# hld.net
KiCad netlist of a schematic drawn in EAGLE
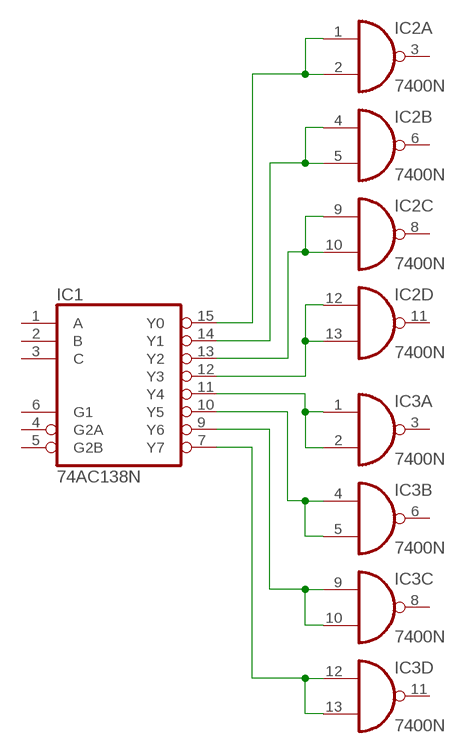
[diagram p0: schematic, sheet 1]

(export (version "E")
  (design (tool "Eeschema 10.0.6"))
  (components
    (comp (ref "IC1")
      (value "74AC138N")
      (footprint "eagle-import:DIL16")
      (libsource (lib "eagle-import") (part "74138NAC"))
    )
    (comp (ref "IC2")
      (value "7400N")
      (footprint "eagle-import:DIL14")
      (libsource (lib "eagle-import") (part "7400N"))
    )
    (comp (ref "IC3")
      (value "7400N")
      (footprint "eagle-import:DIL14")
      (libsource (lib "eagle-import") (part "7400N"))
    )
  )
  (nets
    (net (code "1") (name "Net-(IC1A-Y0)") (class "Default")
      (node (ref "IC1") (pin "15") (pinfunction "Y0_15") (pintype "output"))
      (node (ref "IC2") (pin "1") (pinfunction "I0_1") (pintype "input"))
      (node (ref "IC2") (pin "2") (pinfunction "I1_2") (pintype "input"))
    )
    (net (code "2") (name "Net-(IC1A-Y1)") (class "Default")
      (node (ref "IC1") (pin "14") (pinfunction "Y1_14") (pintype "output"))
      (node (ref "IC2") (pin "4") (pinfunction "I0_4") (pintype "input"))
      (node (ref "IC2") (pin "5") (pinfunction "I1_5") (pintype "input"))
    )
    (net (code "3") (name "Net-(IC1A-Y2)") (class "Default")
      (node (ref "IC1") (pin "13") (pinfunction "Y2_13") (pintype "output"))
      (node (ref "IC2") (pin "10") (pinfunction "I1_10") (pintype "input"))
      (node (ref "IC2") (pin "9") (pinfunction "I0_9") (pintype "input"))
    )
    (net (code "4") (name "Net-(IC1A-Y3)") (class "Default")
      (node (ref "IC1") (pin "12") (pinfunction "Y3_12") (pintype "output"))
      (node (ref "IC2") (pin "12") (pinfunction "I0_12") (pintype "input"))
      (node (ref "IC2") (pin "13") (pinfunction "I1_13") (pintype "input"))
    )
    (net (code "5") (name "Net-(IC1A-Y4)") (class "Default")
      (node (ref "IC1") (pin "11") (pinfunction "Y4_11") (pintype "output"))
      (node (ref "IC3") (pin "1") (pinfunction "I0_1") (pintype "input"))
      (node (ref "IC3") (pin "2") (pinfunction "I1_2") (pintype "input"))
    )
    (net (code "6") (name "Net-(IC1A-Y5)") (class "Default")
      (node (ref "IC1") (pin "10") (pinfunction "Y5_10") (pintype "output"))
      (node (ref "IC3") (pin "4") (pinfunction "I0_4") (pintype "input"))
      (node (ref "IC3") (pin "5") (pinfunction "I1_5") (pintype "input"))
    )
    (net (code "7") (name "Net-(IC1A-Y6)") (class "Default")
      (node (ref "IC1") (pin "9") (pinfunction "Y6_9") (pintype "output"))
      (node (ref "IC3") (pin "10") (pinfunction "I1_10") (pintype "input"))
      (node (ref "IC3") (pin "9") (pinfunction "I0_9") (pintype "input"))
    )
    (net (code "8") (name "Net-(IC1A-Y7)") (class "Default")
      (node (ref "IC1") (pin "7") (pinfunction "Y7_7") (pintype "output"))
      (node (ref "IC3") (pin "12") (pinfunction "I0_12") (pintype "input"))
      (node (ref "IC3") (pin "13") (pinfunction "I1_13") (pintype "input"))
    )
    (net (code "9") (name "unconnected-(IC1A-A-Pad1)") (class "Default")
      (node (ref "IC1") (pin "1") (pinfunction "A_1") (pintype "input"))
    )
    (net (code "10") (name "unconnected-(IC1A-B-Pad2)") (class "Default")
      (node (ref "IC1") (pin "2") (pinfunction "B_2") (pintype "input"))
    )
    (net (code "11") (name "unconnected-(IC1A-C-Pad3)") (class "Default")
      (node (ref "IC1") (pin "3") (pinfunction "C_3") (pintype "input"))
    )
    (net (code "12") (name "unconnected-(IC1A-G1-Pad6)") (class "Default")
      (node (ref "IC1") (pin "6") (pinfunction "G1_6") (pintype "input"))
    )
    (net (code "13") (name "unconnected-(IC1A-G2A-Pad4)") (class "Default")
      (node (ref "IC1") (pin "4") (pinfunction "G2A_4") (pintype "input"))
    )
    (net (code "14") (name "unconnected-(IC1A-G2B-Pad5)") (class "Default")
      (node (ref "IC1") (pin "5") (pinfunction "G2B_5") (pintype "input"))
    )
    (net (code "15") (name "unconnected-(IC2A-O-Pad3)") (class "Default")
      (node (ref "IC2") (pin "3") (pinfunction "O_3") (pintype "output"))
    )
    (net (code "16") (name "unconnected-(IC2B-O-Pad6)") (class "Default")
      (node (ref "IC2") (pin "6") (pinfunction "O_6") (pintype "output"))
    )
    (net (code "17") (name "unconnected-(IC2C-O-Pad8)") (class "Default")
      (node (ref "IC2") (pin "8") (pinfunction "O_8") (pintype "output"))
    )
    (net (code "18") (name "unconnected-(IC2D-O-Pad11)") (class "Default")
      (node (ref "IC2") (pin "11") (pinfunction "O_11") (pintype "output"))
    )
    (net (code "19") (name "unconnected-(IC3A-O-Pad3)") (class "Default")
      (node (ref "IC3") (pin "3") (pinfunction "O_3") (pintype "output"))
    )
    (net (code "20") (name "unconnected-(IC3B-O-Pad6)") (class "Default")
      (node (ref "IC3") (pin "6") (pinfunction "O_6") (pintype "output"))
    )
    (net (code "21") (name "unconnected-(IC3C-O-Pad8)") (class "Default")
      (node (ref "IC3") (pin "8") (pinfunction "O_8") (pintype "output"))
    )
    (net (code "22") (name "unconnected-(IC3D-O-Pad11)") (class "Default")
      (node (ref "IC3") (pin "11") (pinfunction "O_11") (pintype "output"))
    )
  )
)
